# lcd_octopus_t2313_pwm_contrast.net
KiCad netlist of a schematic drawn in EAGLE
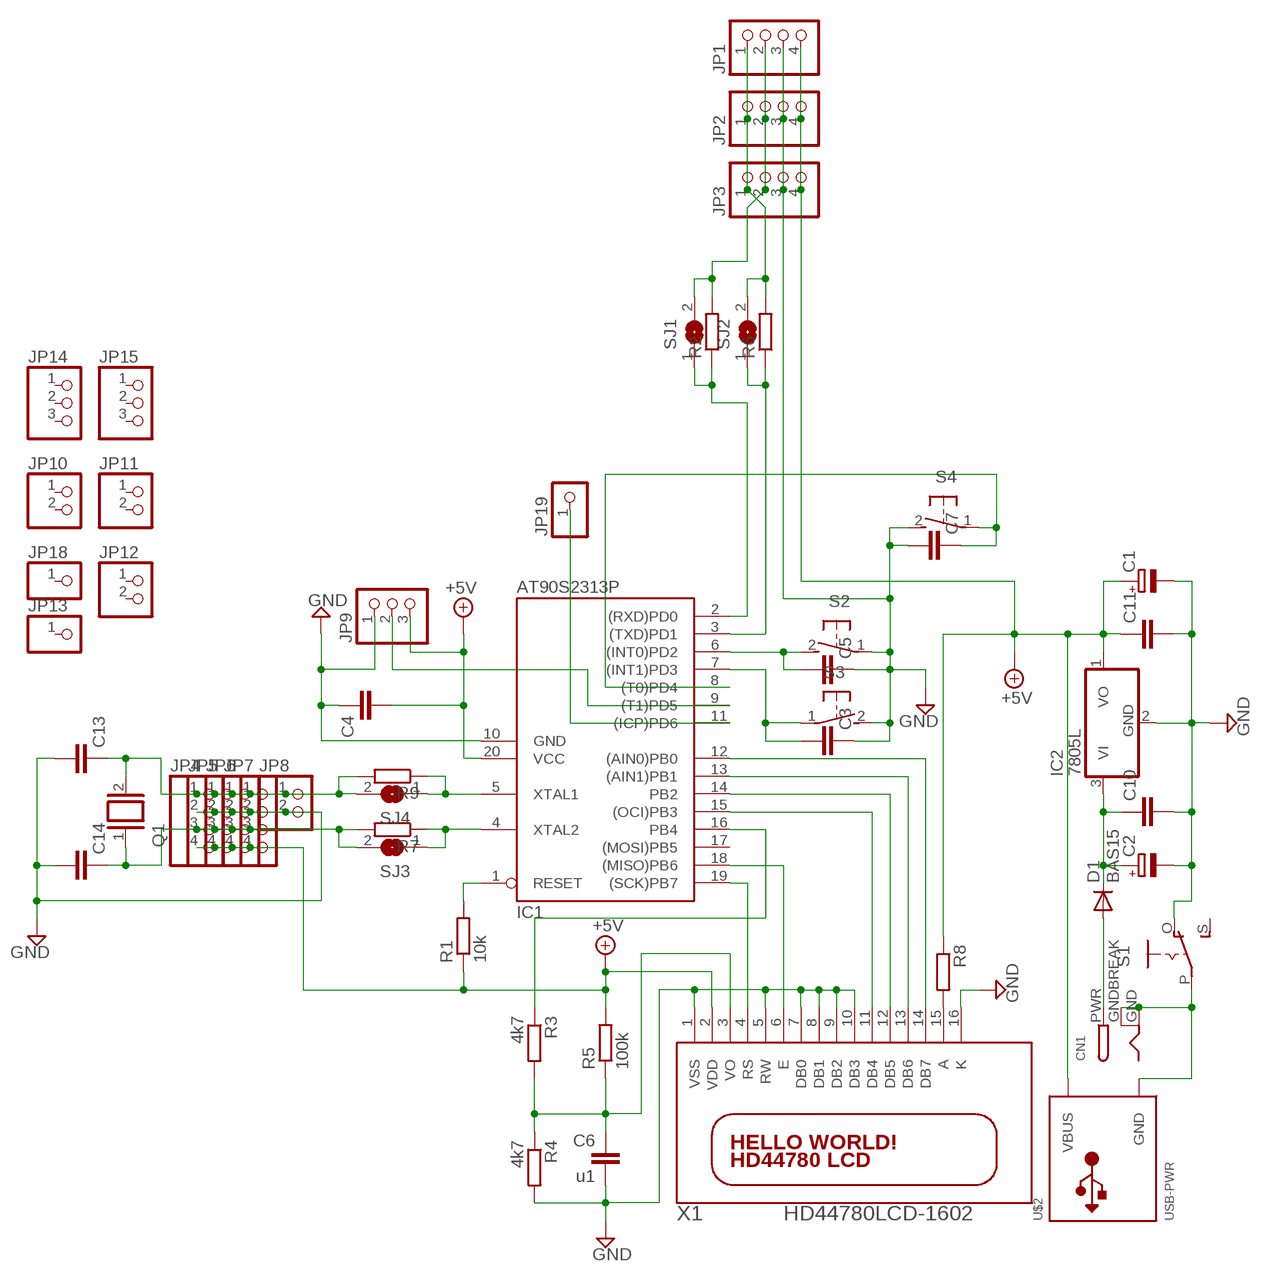
[diagram p0: schematic, sheet 1]

(export (version "E")
  (design (tool "Eeschema 10.0.6"))
  (components
    (comp (ref "C1")
      (value "CPOL-EUTT2D5L")
      (footprint "eagle-import:TT2D5L")
      (libsource (lib "eagle-import") (part "CPOL-EUTT2D5L"))
    )
    (comp (ref "C2")
      (value "CPOL-EUTT2D5L")
      (footprint "eagle-import:TT2D5L")
      (libsource (lib "eagle-import") (part "CPOL-EUTT2D5L"))
    )
    (comp (ref "C3")
      (value "C-EU025-025X050")
      (footprint "eagle-import:C025-025X050")
      (libsource (lib "eagle-import") (part "C-EU025-025X050"))
    )
    (comp (ref "C4")
      (value "C-EU025-025X050")
      (footprint "eagle-import:C025-025X050")
      (libsource (lib "eagle-import") (part "C-EU025-025X050"))
    )
    (comp (ref "C5")
      (value "C-EU025-025X050")
      (footprint "eagle-import:C025-025X050")
      (libsource (lib "eagle-import") (part "C-EU025-025X050"))
    )
    (comp (ref "C6")
      (value "u1")
      (footprint "eagle-import:C025-025X050")
      (libsource (lib "eagle-import") (part "C-EU025-025X050"))
    )
    (comp (ref "C7")
      (value "C-EU025-025X050")
      (footprint "eagle-import:C025-025X050")
      (libsource (lib "eagle-import") (part "C-EU025-025X050"))
    )
    (comp (ref "C10")
      (value "C-EU025-025X050")
      (footprint "eagle-import:C025-025X050")
      (libsource (lib "eagle-import") (part "C-EU025-025X050"))
    )
    (comp (ref "C11")
      (value "C-EU025-025X050")
      (footprint "eagle-import:C025-025X050")
      (libsource (lib "eagle-import") (part "C-EU025-025X050"))
    )
    (comp (ref "C13")
      (value "C-EU025-025X050")
      (footprint "eagle-import:C025-025X050")
      (libsource (lib "eagle-import") (part "C-EU025-025X050"))
    )
    (comp (ref "C14")
      (value "C-EU025-025X050")
      (footprint "eagle-import:C025-025X050")
      (libsource (lib "eagle-import") (part "C-EU025-025X050"))
    )
    (comp (ref "CN1")
      (value "DCBARRELPTH")
      (footprint "eagle-import:DCJACK_2MM_PTH")
      (libsource (lib "eagle-import") (part "DCBARRELPTH"))
    )
    (comp (ref "D1")
      (value "BAS15")
      (footprint "eagle-import:DO34-7")
      (libsource (lib "eagle-import") (part "BAS15"))
    )
    (comp (ref "IC1")
      (value "AT90S2313P")
      (footprint "eagle-import:DIL20")
      (libsource (lib "eagle-import") (part "AT90S2313P"))
    )
    (comp (ref "IC2")
      (value "7805L")
      (footprint "eagle-import:TO92")
      (libsource (lib "eagle-import") (part "78L05"))
    )
    (comp (ref "JP1")
      (value "PINHD-1X4/90")
      (footprint "eagle-import:1X04_90")
      (libsource (lib "eagle-import") (part "PINHD-1X4/90"))
    )
    (comp (ref "JP2")
      (value "PINHD-1X4")
      (footprint "eagle-import:1X04")
      (libsource (lib "eagle-import") (part "PINHD-1X4"))
    )
    (comp (ref "JP3")
      (value "PINHD-1X4")
      (footprint "eagle-import:1X04")
      (libsource (lib "eagle-import") (part "PINHD-1X4"))
    )
    (comp (ref "JP4")
      (value "PINHD-1X4")
      (footprint "eagle-import:1X04")
      (libsource (lib "eagle-import") (part "PINHD-1X4"))
    )
    (comp (ref "JP5")
      (value "PINHD-1X4")
      (footprint "eagle-import:1X04")
      (libsource (lib "eagle-import") (part "PINHD-1X4"))
    )
    (comp (ref "JP6")
      (value "PINHD-1X4")
      (footprint "eagle-import:1X04")
      (libsource (lib "eagle-import") (part "PINHD-1X4"))
    )
    (comp (ref "JP7")
      (value "PINHD-1X4")
      (footprint "eagle-import:1X04")
      (libsource (lib "eagle-import") (part "PINHD-1X4"))
    )
    (comp (ref "JP8")
      (value "PINHD-1X2")
      (footprint "eagle-import:1X02")
      (libsource (lib "eagle-import") (part "PINHD-1X2"))
    )
    (comp (ref "JP9")
      (value "PINHD-1X3")
      (footprint "eagle-import:1X03")
      (libsource (lib "eagle-import") (part "PINHD-1X3"))
    )
    (comp (ref "JP10")
      (value "PINHD-1X2")
      (footprint "eagle-import:1X02")
      (libsource (lib "eagle-import") (part "PINHD-1X2"))
    )
    (comp (ref "JP11")
      (value "PINHD-1X2")
      (footprint "eagle-import:1X02")
      (libsource (lib "eagle-import") (part "PINHD-1X2"))
    )
    (comp (ref "JP12")
      (value "PINHD-1X2")
      (footprint "eagle-import:1X02")
      (libsource (lib "eagle-import") (part "PINHD-1X2"))
    )
    (comp (ref "JP13")
      (value "PINHD-1X1")
      (footprint "eagle-import:1X01")
      (libsource (lib "eagle-import") (part "PINHD-1X1"))
    )
    (comp (ref "JP14")
      (value "PINHD-1X3")
      (footprint "eagle-import:1X03")
      (libsource (lib "eagle-import") (part "PINHD-1X3"))
    )
    (comp (ref "JP15")
      (value "PINHD-1X3")
      (footprint "eagle-import:1X03")
      (libsource (lib "eagle-import") (part "PINHD-1X3"))
    )
    (comp (ref "JP18")
      (value "PINHD-1X1")
      (footprint "eagle-import:1X01")
      (libsource (lib "eagle-import") (part "PINHD-1X1"))
    )
    (comp (ref "JP19")
      (value "PINHD-1X1")
      (footprint "eagle-import:1X01")
      (libsource (lib "eagle-import") (part "PINHD-1X1"))
    )
    (comp (ref "Q1")
      (value "XTAL/S")
      (footprint "eagle-import:QS")
      (libsource (lib "eagle-import") (part "XTAL/S"))
    )
    (comp (ref "R1")
      (value "10k")
      (footprint "eagle-import:0204_7")
      (libsource (lib "eagle-import") (part "R-EU_0204/7"))
    )
    (comp (ref "R2")
      (value "R-EU_0204/7")
      (footprint "eagle-import:0204_7")
      (libsource (lib "eagle-import") (part "R-EU_0204/7"))
    )
    (comp (ref "R3")
      (value "4k7")
      (footprint "eagle-import:0207_12")
      (libsource (lib "eagle-import") (part "R-EU_0207/12"))
    )
    (comp (ref "R4")
      (value "4k7")
      (footprint "eagle-import:0204_7")
      (libsource (lib "eagle-import") (part "R-EU_0204/7"))
    )
    (comp (ref "R5")
      (value "100k")
      (footprint "eagle-import:0204_7")
      (libsource (lib "eagle-import") (part "R-EU_0204/7"))
    )
    (comp (ref "R6")
      (value "R-EU_0204/7")
      (footprint "eagle-import:0204_7")
      (libsource (lib "eagle-import") (part "R-EU_0204/7"))
    )
    (comp (ref "R7")
      (value "R-EU_0204/7")
      (footprint "eagle-import:0204_7")
      (libsource (lib "eagle-import") (part "R-EU_0204/7"))
    )
    (comp (ref "R8")
      (value "R-EU_0204/7")
      (footprint "eagle-import:0204_7")
      (libsource (lib "eagle-import") (part "R-EU_0204/7"))
    )
    (comp (ref "R9")
      (value "R-EU_0204/7")
      (footprint "eagle-import:0204_7")
      (libsource (lib "eagle-import") (part "R-EU_0204/7"))
    )
    (comp (ref "S1")
      (value "EG1218S")
      (footprint "eagle-import:EG1218")
      (libsource (lib "eagle-import") (part "EG1218S"))
    )
    (comp (ref "S2")
      (value "31-XX")
      (footprint "eagle-import:B3F-31XX")
      (libsource (lib "eagle-import") (part "31-XX"))
    )
    (comp (ref "S3")
      (value "31-XX")
      (footprint "eagle-import:B3F-31XX")
      (libsource (lib "eagle-import") (part "31-XX"))
    )
    (comp (ref "S4")
      (value "31-XX")
      (footprint "eagle-import:B3F-31XX")
      (libsource (lib "eagle-import") (part "31-XX"))
    )
    (comp (ref "SJ1") (value "SJ") (footprint "eagle-import:SJ") (libsource (lib "eagle-import") (part "SJ")))
    (comp (ref "SJ2") (value "SJ") (footprint "eagle-import:SJ") (libsource (lib "eagle-import") (part "SJ")))
    (comp (ref "SJ3") (value "SJ") (footprint "eagle-import:SJ") (libsource (lib "eagle-import") (part "SJ")))
    (comp (ref "SJ4") (value "SJ") (footprint "eagle-import:SJ") (libsource (lib "eagle-import") (part "SJ")))
    (comp (ref "U$2")
      (value "USB-PWR")
      (footprint "eagle-import:USB-MINIB-THM-MOLEX-PWRONLY")
      (libsource (lib "eagle-import") (part "USB-PWR"))
    )
    (comp (ref "X1")
      (value "HD44780LCD-1602")
      (footprint "eagle-import:LCD1602")
      (libsource (lib "eagle-import") (part "HD44780LCD-1602"))
    )
  )
  (nets
    (net (code "1") (name "+5V") (class "Default")
      (node (ref "C1") (pin "+") (pinfunction "+_+") (pintype "passive"))
      (node (ref "C11") (pin "1") (pinfunction "1_1") (pintype "passive"))
      (node (ref "C4") (pin "2") (pinfunction "2_2") (pintype "passive"))
      (node (ref "IC1") (pin "20") (pinfunction "VCC_20") (pintype "power_in"))
      (node (ref "IC2") (pin "1") (pinfunction "VO_1") (pintype "passive"))
      (node (ref "JP1") (pin "4") (pinfunction "4_4") (pintype "passive"))
      (node (ref "JP2") (pin "4") (pinfunction "4_4") (pintype "passive"))
      (node (ref "JP3") (pin "4") (pinfunction "4_4") (pintype "passive"))
      (node (ref "JP4") (pin "4") (pinfunction "4_4") (pintype "passive"))
      (node (ref "JP5") (pin "4") (pinfunction "4_4") (pintype "passive"))
      (node (ref "JP6") (pin "4") (pinfunction "4_4") (pintype "passive"))
      (node (ref "JP7") (pin "4") (pinfunction "4_4") (pintype "passive"))
      (node (ref "JP9") (pin "3") (pinfunction "3_3") (pintype "passive"))
      (node (ref "R1") (pin "1") (pinfunction "1_1") (pintype "passive"))
      (node (ref "R5") (pin "2") (pinfunction "2_2") (pintype "passive"))
      (node (ref "R8") (pin "1") (pinfunction "1_1") (pintype "passive"))
      (node (ref "U$2") (pin "VBUS") (pinfunction "VBUS_VBUS") (pintype "power_in"))
      (node (ref "X1") (pin "2") (pinfunction "VDD_2") (pintype "power_in"))
    )
    (net (code "2") (name "GND") (class "Default")
      (node (ref "C1") (pin "-") (pinfunction "-_-") (pintype "passive"))
      (node (ref "C10") (pin "2") (pinfunction "2_2") (pintype "passive"))
      (node (ref "C11") (pin "2") (pinfunction "2_2") (pintype "passive"))
      (node (ref "C13") (pin "2") (pinfunction "2_2") (pintype "passive"))
      (node (ref "C14") (pin "2") (pinfunction "2_2") (pintype "passive"))
      (node (ref "C2") (pin "-") (pinfunction "-_-") (pintype "passive"))
      (node (ref "C3") (pin "1") (pinfunction "1_1") (pintype "passive"))
      (node (ref "C4") (pin "1") (pinfunction "1_1") (pintype "passive"))
      (node (ref "C5") (pin "1") (pinfunction "1_1") (pintype "passive"))
      (node (ref "C6") (pin "2") (pinfunction "2_2") (pintype "passive"))
      (node (ref "C7") (pin "2") (pinfunction "2_2") (pintype "passive"))
      (node (ref "IC1") (pin "10") (pinfunction "GND_10") (pintype "power_in"))
      (node (ref "IC2") (pin "2") (pinfunction "GND_2") (pintype "passive"))
      (node (ref "JP1") (pin "3") (pinfunction "3_3") (pintype "passive"))
      (node (ref "JP2") (pin "3") (pinfunction "3_3") (pintype "passive"))
      (node (ref "JP3") (pin "3") (pinfunction "3_3") (pintype "passive"))
      (node (ref "JP4") (pin "2") (pinfunction "2_2") (pintype "passive"))
      (node (ref "JP5") (pin "2") (pinfunction "2_2") (pintype "passive"))
      (node (ref "JP6") (pin "2") (pinfunction "2_2") (pintype "passive"))
      (node (ref "JP7") (pin "2") (pinfunction "2_2") (pintype "passive"))
      (node (ref "JP8") (pin "2") (pinfunction "2_2") (pintype "passive"))
      (node (ref "JP9") (pin "1") (pinfunction "1_1") (pintype "passive"))
      (node (ref "R4") (pin "2") (pinfunction "2_2") (pintype "passive"))
      (node (ref "S1") (pin "O") (pinfunction "O_O") (pintype "passive"))
      (node (ref "S2") (pin "1") (pinfunction "P_1") (pintype "passive"))
      (node (ref "S3") (pin "2") (pinfunction "S_2") (pintype "passive"))
      (node (ref "S4") (pin "2") (pinfunction "S_2") (pintype "passive"))
      (node (ref "X1") (pin "1") (pinfunction "VSS_1") (pintype "power_in"))
      (node (ref "X1") (pin "10") (pinfunction "DB3_10") (pintype "bidirectional"))
      (node (ref "X1") (pin "16") (pinfunction "K_16") (pintype "input"))
      (node (ref "X1") (pin "5") (pinfunction "RW_5") (pintype "input"))
      (node (ref "X1") (pin "7") (pinfunction "DB0_7") (pintype "bidirectional"))
      (node (ref "X1") (pin "8") (pinfunction "DB1_8") (pintype "bidirectional"))
      (node (ref "X1") (pin "9") (pinfunction "DB2_9") (pintype "bidirectional"))
    )
    (net (code "3") (name "Net-(C13-Pad1)") (class "Default")
      (node (ref "C13") (pin "1") (pinfunction "1_1") (pintype "passive"))
      (node (ref "JP4") (pin "1") (pinfunction "1_1") (pintype "passive"))
      (node (ref "JP5") (pin "1") (pinfunction "1_1") (pintype "passive"))
      (node (ref "JP6") (pin "1") (pinfunction "1_1") (pintype "passive"))
      (node (ref "JP7") (pin "1") (pinfunction "1_1") (pintype "passive"))
      (node (ref "JP8") (pin "1") (pinfunction "1_1") (pintype "passive"))
      (node (ref "Q1") (pin "2") (pinfunction "2_2") (pintype "passive"))
      (node (ref "R9") (pin "2") (pinfunction "2_2") (pintype "passive"))
      (node (ref "SJ4") (pin "2") (pinfunction "2_2") (pintype "passive"))
    )
    (net (code "4") (name "Net-(C14-Pad1)") (class "Default")
      (node (ref "C14") (pin "1") (pinfunction "1_1") (pintype "passive"))
      (node (ref "JP4") (pin "3") (pinfunction "3_3") (pintype "passive"))
      (node (ref "JP5") (pin "3") (pinfunction "3_3") (pintype "passive"))
      (node (ref "JP6") (pin "3") (pinfunction "3_3") (pintype "passive"))
      (node (ref "JP7") (pin "3") (pinfunction "3_3") (pintype "passive"))
      (node (ref "Q1") (pin "1") (pinfunction "1_1") (pintype "passive"))
      (node (ref "R7") (pin "2") (pinfunction "2_2") (pintype "passive"))
      (node (ref "SJ3") (pin "2") (pinfunction "2_2") (pintype "passive"))
    )
    (net (code "5") (name "Net-(CN1-PadGND)") (class "Default")
      (node (ref "CN1") (pin "GND") (pinfunction "GND_GND") (pintype "power_in"))
      (node (ref "CN1") (pin "GNDBREAK") (pinfunction "GNDBREAK_GNDBREAK") (pintype "power_in"))
      (node (ref "S1") (pin "P") (pinfunction "P_P") (pintype "passive"))
      (node (ref "U$2") (pin "GND") (pinfunction "GND_GND") (pintype "power_in"))
    )
    (net (code "6") (name "Net-(CN1-PadPWR)") (class "Default")
      (node (ref "CN1") (pin "PWR") (pinfunction "PWR_PWR") (pintype "power_in"))
      (node (ref "D1") (pin "A") (pinfunction "A_A") (pintype "passive"))
    )
    (net (code "7") (name "Net-(IC1-(AIN0)PB0)") (class "Default")
      (node (ref "IC1") (pin "12") (pinfunction "(AIN0)PB0_12") (pintype "bidirectional"))
      (node (ref "X1") (pin "14") (pinfunction "DB7_14") (pintype "bidirectional"))
    )
    (net (code "8") (name "Net-(IC1-(AIN1)PB1)") (class "Default")
      (node (ref "IC1") (pin "13") (pinfunction "(AIN1)PB1_13") (pintype "bidirectional"))
      (node (ref "X1") (pin "13") (pinfunction "DB6_13") (pintype "bidirectional"))
    )
    (net (code "9") (name "Net-(IC1-(ICP)PD6)") (class "Default")
      (node (ref "IC1") (pin "11") (pinfunction "(ICP)PD6_11") (pintype "bidirectional"))
      (node (ref "JP19") (pin "1") (pinfunction "1_1") (pintype "passive"))
    )
    (net (code "10") (name "Net-(IC1-(INT0)PD2)") (class "Default")
      (node (ref "C5") (pin "2") (pinfunction "2_2") (pintype "passive"))
      (node (ref "IC1") (pin "6") (pinfunction "(INT0)PD2_6") (pintype "bidirectional"))
      (node (ref "S2") (pin "2") (pinfunction "S_2") (pintype "passive"))
    )
    (net (code "11") (name "Net-(IC1-(INT1)PD3)") (class "Default")
      (node (ref "C3") (pin "2") (pinfunction "2_2") (pintype "passive"))
      (node (ref "IC1") (pin "7") (pinfunction "(INT1)PD3_7") (pintype "bidirectional"))
      (node (ref "S3") (pin "1") (pinfunction "P_1") (pintype "passive"))
    )
    (net (code "12") (name "Net-(IC1-(MISO)PB6)") (class "Default")
      (node (ref "IC1") (pin "18") (pinfunction "(MISO)PB6_18") (pintype "bidirectional"))
      (node (ref "X1") (pin "6") (pinfunction "E_6") (pintype "input"))
    )
    (net (code "13") (name "Net-(IC1-(OCI)PB3)") (class "Default")
      (node (ref "IC1") (pin "15") (pinfunction "(OCI)PB3_15") (pintype "bidirectional"))
      (node (ref "X1") (pin "11") (pinfunction "DB4_11") (pintype "bidirectional"))
    )
    (net (code "14") (name "Net-(IC1-(RXD)PD0)") (class "Default")
      (node (ref "IC1") (pin "2") (pinfunction "(RXD)PD0_2") (pintype "bidirectional"))
      (node (ref "R2") (pin "1") (pinfunction "1_1") (pintype "passive"))
      (node (ref "SJ1") (pin "1") (pinfunction "1_1") (pintype "passive"))
    )
    (net (code "15") (name "Net-(IC1-(SCK)PB7)") (class "Default")
      (node (ref "IC1") (pin "19") (pinfunction "(SCK)PB7_19") (pintype "bidirectional"))
      (node (ref "X1") (pin "4") (pinfunction "RS_4") (pintype "input"))
    )
    (net (code "16") (name "Net-(IC1-(T0)PD4)") (class "Default")
      (node (ref "C7") (pin "1") (pinfunction "1_1") (pintype "passive"))
      (node (ref "IC1") (pin "8") (pinfunction "(T0)PD4_8") (pintype "bidirectional"))
      (node (ref "S4") (pin "1") (pinfunction "P_1") (pintype "passive"))
    )
    (net (code "17") (name "Net-(IC1-(T1)PD5)") (class "Default")
      (node (ref "IC1") (pin "9") (pinfunction "(T1)PD5_9") (pintype "bidirectional"))
      (node (ref "JP9") (pin "2") (pinfunction "2_2") (pintype "passive"))
    )
    (net (code "18") (name "Net-(IC1-(TXD)PD1)") (class "Default")
      (node (ref "IC1") (pin "3") (pinfunction "(TXD)PD1_3") (pintype "bidirectional"))
      (node (ref "R6") (pin "1") (pinfunction "1_1") (pintype "passive"))
      (node (ref "SJ2") (pin "1") (pinfunction "1_1") (pintype "passive"))
    )
    (net (code "19") (name "Net-(IC1-PB2)") (class "Default")
      (node (ref "IC1") (pin "14") (pinfunction "PB2_14") (pintype "bidirectional"))
      (node (ref "X1") (pin "12") (pinfunction "DB5_12") (pintype "bidirectional"))
    )
    (net (code "20") (name "Net-(IC1-PB4)") (class "Default")
      (node (ref "IC1") (pin "16") (pinfunction "PB4_16") (pintype "bidirectional"))
      (node (ref "R3") (pin "1") (pinfunction "1_1") (pintype "passive"))
    )
    (net (code "21") (name "Net-(IC1-RESET)") (class "Default")
      (node (ref "IC1") (pin "1") (pinfunction "RESET_1") (pintype "bidirectional"))
      (node (ref "R1") (pin "2") (pinfunction "2_2") (pintype "passive"))
    )
    (net (code "22") (name "Net-(IC1-XTAL1)") (class "Default")
      (node (ref "IC1") (pin "5") (pinfunction "XTAL1_5") (pintype "bidirectional"))
      (node (ref "R9") (pin "1") (pinfunction "1_1") (pintype "passive"))
      (node (ref "SJ4") (pin "1") (pinfunction "1_1") (pintype "passive"))
    )
    (net (code "23") (name "Net-(IC1-XTAL2)") (class "Default")
      (node (ref "IC1") (pin "4") (pinfunction "XTAL2_4") (pintype "bidirectional"))
      (node (ref "R7") (pin "1") (pinfunction "1_1") (pintype "passive"))
      (node (ref "SJ3") (pin "1") (pinfunction "1_1") (pintype "passive"))
    )
    (net (code "24") (name "Net-(IC2-VI)") (class "Default")
      (node (ref "C10") (pin "1") (pinfunction "1_1") (pintype "passive"))
      (node (ref "C2") (pin "+") (pinfunction "+_+") (pintype "passive"))
      (node (ref "D1") (pin "C") (pinfunction "C_C") (pintype "passive"))
      (node (ref "IC2") (pin "3") (pinfunction "VI_3") (pintype "input"))
    )
    (net (code "25") (name "Net-(JP1-Pad1)") (class "Default")
      (node (ref "JP1") (pin "1") (pinfunction "1_1") (pintype "passive"))
      (node (ref "JP2") (pin "1") (pinfunction "1_1") (pintype "passive"))
      (node (ref "JP3") (pin "1") (pinfunction "1_1") (pintype "passive"))
      (node (ref "R6") (pin "2") (pinfunction "2_2") (pintype "passive"))
      (node (ref "SJ2") (pin "2") (pinfunction "2_2") (pintype "passive"))
    )
    (net (code "26") (name "Net-(JP1-Pad2)") (class "Default")
      (node (ref "JP1") (pin "2") (pinfunction "2_2") (pintype "passive"))
      (node (ref "JP2") (pin "2") (pinfunction "2_2") (pintype "passive"))
      (node (ref "JP3") (pin "2") (pinfunction "2_2") (pintype "passive"))
      (node (ref "R2") (pin "2") (pinfunction "2_2") (pintype "passive"))
      (node (ref "SJ1") (pin "2") (pinfunction "2_2") (pintype "passive"))
    )
    (net (code "27") (name "Net-(X1-A)") (class "Default")
      (node (ref "R8") (pin "2") (pinfunction "2_2") (pintype "passive"))
      (node (ref "X1") (pin "15") (pinfunction "A_15") (pintype "input"))
    )
    (net (code "28") (name "Net-(X1-VO)") (class "Default")
      (node (ref "C6") (pin "1") (pinfunction "1_1") (pintype "passive"))
      (node (ref "R3") (pin "2") (pinfunction "2_2") (pintype "passive"))
      (node (ref "R4") (pin "1") (pinfunction "1_1") (pintype "passive"))
      (node (ref "R5") (pin "1") (pinfunction "1_1") (pintype "passive"))
      (node (ref "X1") (pin "3") (pinfunction "VO_3") (pintype "input"))
    )
    (net (code "29") (name "unconnected-(IC1-(MOSI)PB5-Pad17)") (class "Default")
      (node (ref "IC1") (pin "17") (pinfunction "(MOSI)PB5_17") (pintype "bidirectional"))
    )
    (net (code "30") (name "unconnected-(JP10-Pad1)") (class "Default")
      (node (ref "JP10") (pin "1") (pinfunction "1_1") (pintype "passive"))
    )
    (net (code "31") (name "unconnected-(JP10-Pad2)") (class "Default")
      (node (ref "JP10") (pin "2") (pinfunction "2_2") (pintype "passive"))
    )
    (net (code "32") (name "unconnected-(JP11-Pad1)") (class "Default")
      (node (ref "JP11") (pin "1") (pinfunction "1_1") (pintype "passive"))
    )
    (net (code "33") (name "unconnected-(JP11-Pad2)") (class "Default")
      (node (ref "JP11") (pin "2") (pinfunction "2_2") (pintype "passive"))
    )
    (net (code "34") (name "unconnected-(JP12-Pad1)") (class "Default")
      (node (ref "JP12") (pin "1") (pinfunction "1_1") (pintype "passive"))
    )
    (net (code "35") (name "unconnected-(JP12-Pad2)") (class "Default")
      (node (ref "JP12") (pin "2") (pinfunction "2_2") (pintype "passive"))
    )
    (net (code "36") (name "unconnected-(JP13-Pad1)") (class "Default")
      (node (ref "JP13") (pin "1") (pinfunction "1_1") (pintype "passive"))
    )
    (net (code "37") (name "unconnected-(JP14-Pad1)") (class "Default")
      (node (ref "JP14") (pin "1") (pinfunction "1_1") (pintype "passive"))
    )
    (net (code "38") (name "unconnected-(JP14-Pad2)") (class "Default")
      (node (ref "JP14") (pin "2") (pinfunction "2_2") (pintype "passive"))
    )
    (net (code "39") (name "unconnected-(JP14-Pad3)") (class "Default")
      (node (ref "JP14") (pin "3") (pinfunction "3_3") (pintype "passive"))
    )
    (net (code "40") (name "unconnected-(JP15-Pad1)") (class "Default")
      (node (ref "JP15") (pin "1") (pinfunction "1_1") (pintype "passive"))
    )
    (net (code "41") (name "unconnected-(JP15-Pad2)") (class "Default")
      (node (ref "JP15") (pin "2") (pinfunction "2_2") (pintype "passive"))
    )
    (net (code "42") (name "unconnected-(JP15-Pad3)") (class "Default")
      (node (ref "JP15") (pin "3") (pinfunction "3_3") (pintype "passive"))
    )
    (net (code "43") (name "unconnected-(JP18-Pad1)") (class "Default")
      (node (ref "JP18") (pin "1") (pinfunction "1_1") (pintype "passive"))
    )
    (net (code "44") (name "unconnected-(S1-PadS)") (class "Default")
      (node (ref "S1") (pin "S") (pinfunction "S_S") (pintype "passive"))
    )
  )
)
